# LumaFix64_Vic85to65.net
KiCad netlist of a schematic drawn in EAGLE
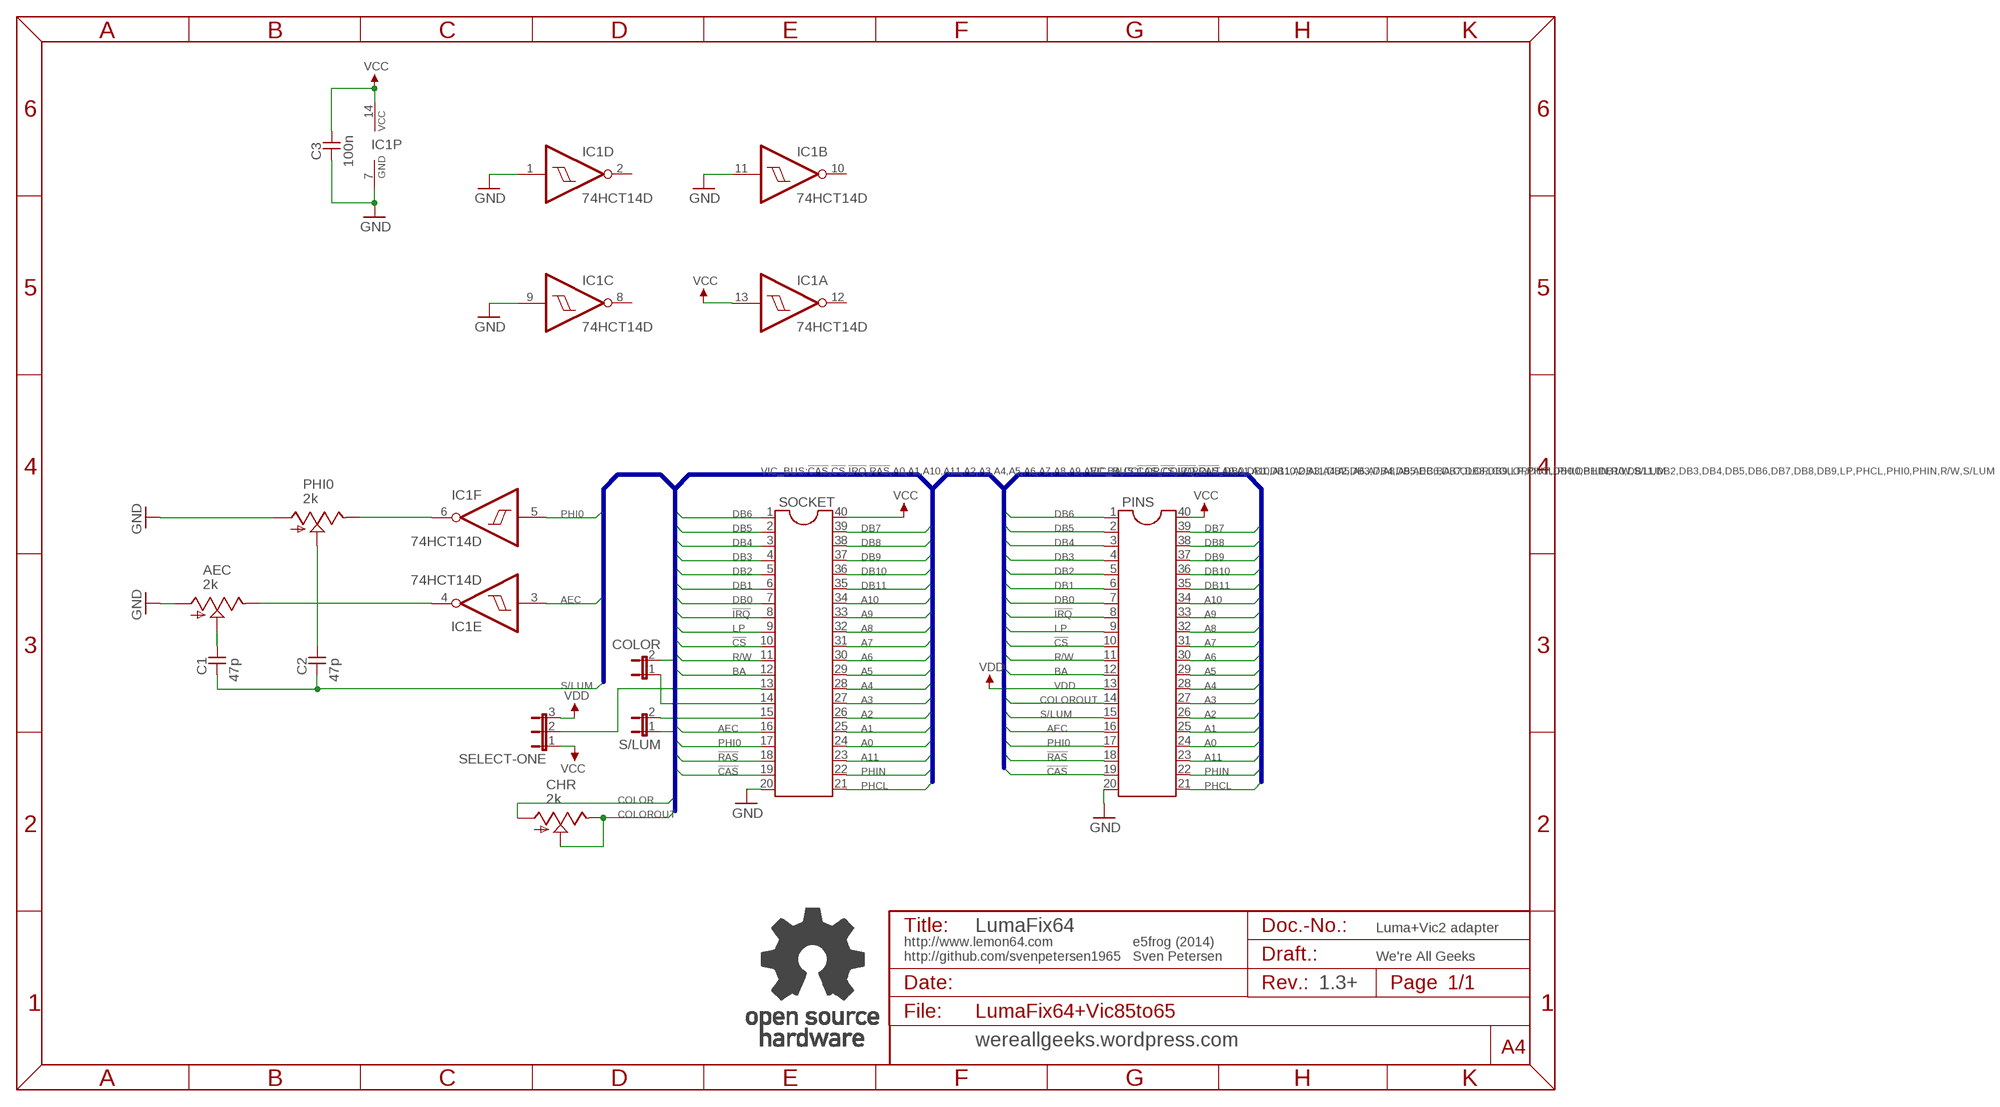
[diagram p0: schematic, sheet 1]

(export (version "E")
  (design (tool "Eeschema 10.0.6"))
  (components
    (comp (ref "AEC")
      (value "2k")
      (footprint "eagle-import:RJ9W")
      (libsource (lib "eagle-import") (part "TRIM_US-RJ9W"))
    )
    (comp (ref "C1")
      (value "47p")
      (footprint "eagle-import:0805")
      (libsource (lib "eagle-import") (part "C-0805"))
    )
    (comp (ref "C2")
      (value "47p")
      (footprint "eagle-import:0805")
      (libsource (lib "eagle-import") (part "C-0805"))
    )
    (comp (ref "C3")
      (value "100n")
      (footprint "eagle-import:0805")
      (libsource (lib "eagle-import") (part "C-0805"))
    )
    (comp (ref "CHR")
      (value "2k")
      (footprint "eagle-import:RJ9W")
      (libsource (lib "eagle-import") (part "TRIM_US-RJ9W"))
    )
    (comp (ref "COLOR")
      (value "JP1E")
      (footprint "eagle-import:JP1")
      (libsource (lib "eagle-import") (part "JP1E"))
    )
    (comp (ref "IC1")
      (value "74HCT14D")
      (footprint "eagle-import:SO14")
      (libsource (lib "eagle-import") (part "7414DHCT"))
    )
    (comp (ref "PHI0")
      (value "2k")
      (footprint "eagle-import:RJ9W")
      (libsource (lib "eagle-import") (part "TRIM_US-RJ9W"))
    )
    (comp (ref "PINS")
      (value "IC-PACKAGE_DIL40_10120540")
      (footprint "eagle-import:BLK_10120540_2X20")
      (libsource (lib "eagle-import") (part "IC-PACKAGE_DIL40_10120540"))
    )
    (comp (ref "S/LUM")
      (value "JP1E")
      (footprint "eagle-import:JP1")
      (libsource (lib "eagle-import") (part "JP1E"))
    )
    (comp (ref "SELECT-ONE")
      (value "JP2E")
      (footprint "eagle-import:JP2")
      (libsource (lib "eagle-import") (part "JP2E"))
    )
    (comp (ref "SOCKET")
      (value "IC-PACKAGE_DIL40GS40P")
      (footprint "eagle-import:GS40P")
      (libsource (lib "eagle-import") (part "IC-PACKAGE_DIL40GS40P"))
    )
    (comp (ref "U$13")
      (value "OPEN_SOURCE_HW")
      (footprint "eagle-import:OPENHW")
      (libsource (lib "eagle-import") (part "OPEN_SOURCE_HW"))
    )
  )
  (nets
    (net (code "2") (name "/A0") (class "Default")
      (node (ref "PINS") (pin "24") (pinfunction "24_24") (pintype "passive"))
      (node (ref "SOCKET") (pin "24") (pinfunction "24_24") (pintype "passive"))
    )
    (net (code "3") (name "/A1") (class "Default")
      (node (ref "PINS") (pin "25") (pinfunction "25_25") (pintype "passive"))
      (node (ref "SOCKET") (pin "25") (pinfunction "25_25") (pintype "passive"))
    )
    (net (code "4") (name "/A2") (class "Default")
      (node (ref "PINS") (pin "26") (pinfunction "26_26") (pintype "passive"))
      (node (ref "SOCKET") (pin "26") (pinfunction "26_26") (pintype "passive"))
    )
    (net (code "5") (name "/A3") (class "Default")
      (node (ref "PINS") (pin "27") (pinfunction "27_27") (pintype "passive"))
      (node (ref "SOCKET") (pin "27") (pinfunction "27_27") (pintype "passive"))
    )
    (net (code "6") (name "/A4") (class "Default")
      (node (ref "PINS") (pin "28") (pinfunction "28_28") (pintype "passive"))
      (node (ref "SOCKET") (pin "28") (pinfunction "28_28") (pintype "passive"))
    )
    (net (code "7") (name "/A5") (class "Default")
      (node (ref "PINS") (pin "29") (pinfunction "29_29") (pintype "passive"))
      (node (ref "SOCKET") (pin "29") (pinfunction "29_29") (pintype "passive"))
    )
    (net (code "8") (name "/A6") (class "Default")
      (node (ref "PINS") (pin "30") (pinfunction "30_30") (pintype "passive"))
      (node (ref "SOCKET") (pin "30") (pinfunction "30_30") (pintype "passive"))
    )
    (net (code "9") (name "/A7") (class "Default")
      (node (ref "PINS") (pin "31") (pinfunction "31_31") (pintype "passive"))
      (node (ref "SOCKET") (pin "31") (pinfunction "31_31") (pintype "passive"))
    )
    (net (code "10") (name "/A8") (class "Default")
      (node (ref "PINS") (pin "32") (pinfunction "32_32") (pintype "passive"))
      (node (ref "SOCKET") (pin "32") (pinfunction "32_32") (pintype "passive"))
    )
    (net (code "11") (name "/A9") (class "Default")
      (node (ref "PINS") (pin "33") (pinfunction "33_33") (pintype "passive"))
      (node (ref "SOCKET") (pin "33") (pinfunction "33_33") (pintype "passive"))
    )
    (net (code "12") (name "/A10") (class "Default")
      (node (ref "PINS") (pin "34") (pinfunction "34_34") (pintype "passive"))
      (node (ref "SOCKET") (pin "34") (pinfunction "34_34") (pintype "passive"))
    )
    (net (code "13") (name "/A11") (class "Default")
      (node (ref "PINS") (pin "23") (pinfunction "23_23") (pintype "passive"))
      (node (ref "SOCKET") (pin "23") (pinfunction "23_23") (pintype "passive"))
    )
    (net (code "14") (name "/AEC") (class "Default")
      (node (ref "IC1") (pin "3") (pinfunction "I_3") (pintype "input"))
      (node (ref "PINS") (pin "16") (pinfunction "16_16") (pintype "passive"))
      (node (ref "SOCKET") (pin "16") (pinfunction "16_16") (pintype "passive"))
    )
    (net (code "15") (name "/BA") (class "Default")
      (node (ref "PINS") (pin "12") (pinfunction "12_12") (pintype "passive"))
      (node (ref "SOCKET") (pin "12") (pinfunction "12_12") (pintype "passive"))
    )
    (net (code "16") (name "/COLOR") (class "Default")
      (node (ref "CHR") (pin "A") (pinfunction "A_A") (pintype "passive"))
      (node (ref "COLOR") (pin "2") (pinfunction "2_2") (pintype "passive"))
    )
    (net (code "17") (name "/COLOROUT") (class "Default")
      (node (ref "CHR") (pin "E") (pinfunction "E_E") (pintype "passive"))
      (node (ref "CHR") (pin "S") (pinfunction "S_S") (pintype "passive"))
      (node (ref "PINS") (pin "14") (pinfunction "14_14") (pintype "passive"))
    )
    (net (code "18") (name "/DB0") (class "Default")
      (node (ref "PINS") (pin "7") (pinfunction "7_7") (pintype "passive"))
      (node (ref "SOCKET") (pin "7") (pinfunction "7_7") (pintype "passive"))
    )
    (net (code "19") (name "/DB1") (class "Default")
      (node (ref "PINS") (pin "6") (pinfunction "6_6") (pintype "passive"))
      (node (ref "SOCKET") (pin "6") (pinfunction "6_6") (pintype "passive"))
    )
    (net (code "20") (name "/DB2") (class "Default")
      (node (ref "PINS") (pin "5") (pinfunction "5_5") (pintype "passive"))
      (node (ref "SOCKET") (pin "5") (pinfunction "5_5") (pintype "passive"))
    )
    (net (code "21") (name "/DB3") (class "Default")
      (node (ref "PINS") (pin "4") (pinfunction "4_4") (pintype "passive"))
      (node (ref "SOCKET") (pin "4") (pinfunction "4_4") (pintype "passive"))
    )
    (net (code "22") (name "/DB4") (class "Default")
      (node (ref "PINS") (pin "3") (pinfunction "3_3") (pintype "passive"))
      (node (ref "SOCKET") (pin "3") (pinfunction "3_3") (pintype "passive"))
    )
    (net (code "23") (name "/DB5") (class "Default")
      (node (ref "PINS") (pin "2") (pinfunction "2_2") (pintype "passive"))
      (node (ref "SOCKET") (pin "2") (pinfunction "2_2") (pintype "passive"))
    )
    (net (code "24") (name "/DB6") (class "Default")
      (node (ref "PINS") (pin "1") (pinfunction "1_1") (pintype "passive"))
      (node (ref "SOCKET") (pin "1") (pinfunction "1_1") (pintype "passive"))
    )
    (net (code "25") (name "/DB7") (class "Default")
      (node (ref "PINS") (pin "39") (pinfunction "39_39") (pintype "passive"))
      (node (ref "SOCKET") (pin "39") (pinfunction "39_39") (pintype "passive"))
    )
    (net (code "26") (name "/DB8") (class "Default")
      (node (ref "PINS") (pin "38") (pinfunction "38_38") (pintype "passive"))
      (node (ref "SOCKET") (pin "38") (pinfunction "38_38") (pintype "passive"))
    )
    (net (code "27") (name "/DB9") (class "Default")
      (node (ref "PINS") (pin "37") (pinfunction "37_37") (pintype "passive"))
      (node (ref "SOCKET") (pin "37") (pinfunction "37_37") (pintype "passive"))
    )
    (net (code "28") (name "/DB10") (class "Default")
      (node (ref "PINS") (pin "36") (pinfunction "36_36") (pintype "passive"))
      (node (ref "SOCKET") (pin "36") (pinfunction "36_36") (pintype "passive"))
    )
    (net (code "29") (name "/DB11") (class "Default")
      (node (ref "PINS") (pin "35") (pinfunction "35_35") (pintype "passive"))
      (node (ref "SOCKET") (pin "35") (pinfunction "35_35") (pintype "passive"))
    )
    (net (code "30") (name "/LP") (class "Default")
      (node (ref "PINS") (pin "9") (pinfunction "9_9") (pintype "passive"))
      (node (ref "SOCKET") (pin "9") (pinfunction "9_9") (pintype "passive"))
    )
    (net (code "31") (name "/PHCL") (class "Default")
      (node (ref "PINS") (pin "21") (pinfunction "21_21") (pintype "passive"))
      (node (ref "SOCKET") (pin "21") (pinfunction "21_21") (pintype "passive"))
    )
    (net (code "32") (name "/PHI0") (class "Default")
      (node (ref "IC1") (pin "5") (pinfunction "I_5") (pintype "input"))
      (node (ref "PINS") (pin "17") (pinfunction "17_17") (pintype "passive"))
      (node (ref "SOCKET") (pin "17") (pinfunction "17_17") (pintype "passive"))
    )
    (net (code "33") (name "/PHIN") (class "Default")
      (node (ref "PINS") (pin "22") (pinfunction "22_22") (pintype "passive"))
      (node (ref "SOCKET") (pin "22") (pinfunction "22_22") (pintype "passive"))
    )
    (net (code "34") (name "/R{slash}W") (class "Default")
      (node (ref "PINS") (pin "11") (pinfunction "11_11") (pintype "passive"))
      (node (ref "SOCKET") (pin "11") (pinfunction "11_11") (pintype "passive"))
    )
    (net (code "35") (name "/VIC_BUS:~{CAS}") (class "Default")
      (node (ref "C1") (pin "1") (pinfunction "1_1") (pintype "passive"))
      (node (ref "C2") (pin "1") (pinfunction "1_1") (pintype "passive"))
      (node (ref "PINS") (pin "15") (pinfunction "15_15") (pintype "passive"))
      (node (ref "S/LUM") (pin "1") (pinfunction "1_1") (pintype "passive"))
    )
    (net (code "37") (name "/~{CAS}") (class "Default")
      (node (ref "PINS") (pin "19") (pinfunction "19_19") (pintype "passive"))
      (node (ref "SOCKET") (pin "19") (pinfunction "19_19") (pintype "passive"))
    )
    (net (code "38") (name "/~{CS}") (class "Default")
      (node (ref "PINS") (pin "10") (pinfunction "10_10") (pintype "passive"))
      (node (ref "SOCKET") (pin "10") (pinfunction "10_10") (pintype "passive"))
    )
    (net (code "39") (name "/~{IRQ}") (class "Default")
      (node (ref "PINS") (pin "8") (pinfunction "8_8") (pintype "passive"))
      (node (ref "SOCKET") (pin "8") (pinfunction "8_8") (pintype "passive"))
    )
    (net (code "40") (name "/~{RAS}") (class "Default")
      (node (ref "PINS") (pin "18") (pinfunction "18_18") (pintype "passive"))
      (node (ref "SOCKET") (pin "18") (pinfunction "18_18") (pintype "passive"))
    )
    (net (code "41") (name "GND") (class "Default")
      (node (ref "AEC") (pin "A") (pinfunction "A_A") (pintype "passive"))
      (node (ref "C3") (pin "1") (pinfunction "1_1") (pintype "passive"))
      (node (ref "IC1") (pin "1") (pinfunction "I_1") (pintype "input"))
      (node (ref "IC1") (pin "11") (pinfunction "I_11") (pintype "input"))
      (node (ref "IC1") (pin "7") (pinfunction "GND_7") (pintype "power_in"))
      (node (ref "IC1") (pin "9") (pinfunction "I_9") (pintype "input"))
      (node (ref "PHI0") (pin "A") (pinfunction "A_A") (pintype "passive"))
      (node (ref "PINS") (pin "20") (pinfunction "20_20") (pintype "passive"))
      (node (ref "SOCKET") (pin "20") (pinfunction "20_20") (pintype "passive"))
    )
    (net (code "42") (name "Net-(AEC-PadS)") (class "Default")
      (node (ref "AEC") (pin "S") (pinfunction "S_S") (pintype "passive"))
      (node (ref "C1") (pin "2") (pinfunction "2_2") (pintype "passive"))
    )
    (net (code "43") (name "Net-(C2-Pad2)") (class "Default")
      (node (ref "C2") (pin "2") (pinfunction "2_2") (pintype "passive"))
      (node (ref "PHI0") (pin "S") (pinfunction "S_S") (pintype "passive"))
    )
    (net (code "44") (name "Net-(COLOR-Pad1)") (class "Default")
      (node (ref "COLOR") (pin "1") (pinfunction "1_1") (pintype "passive"))
      (node (ref "SOCKET") (pin "14") (pinfunction "14_14") (pintype "passive"))
    )
    (net (code "45") (name "Net-(IC1E-O)") (class "Default")
      (node (ref "AEC") (pin "E") (pinfunction "E_E") (pintype "passive"))
      (node (ref "IC1") (pin "4") (pinfunction "O_4") (pintype "output"))
    )
    (net (code "46") (name "Net-(IC1F-O)") (class "Default")
      (node (ref "IC1") (pin "6") (pinfunction "O_6") (pintype "output"))
      (node (ref "PHI0") (pin "E") (pinfunction "E_E") (pintype "passive"))
    )
    (net (code "47") (name "Net-(S/LUM-Pad2)") (class "Default")
      (node (ref "S/LUM") (pin "2") (pinfunction "2_2") (pintype "passive"))
      (node (ref "SOCKET") (pin "15") (pinfunction "15_15") (pintype "passive"))
    )
    (net (code "48") (name "Net-(SELECT-ONE-Pad2)") (class "Default")
      (node (ref "SELECT-ONE") (pin "2") (pinfunction "2_2") (pintype "passive"))
      (node (ref "SOCKET") (pin "13") (pinfunction "13_13") (pintype "passive"))
    )
    (net (code "49") (name "VCC") (class "Default")
      (node (ref "C3") (pin "2") (pinfunction "2_2") (pintype "passive"))
      (node (ref "IC1") (pin "13") (pinfunction "I_13") (pintype "input"))
      (node (ref "IC1") (pin "14") (pinfunction "VCC_14") (pintype "power_in"))
      (node (ref "PINS") (pin "40") (pinfunction "40_40") (pintype "passive"))
      (node (ref "SELECT-ONE") (pin "1") (pinfunction "1_1") (pintype "passive"))
      (node (ref "SOCKET") (pin "40") (pinfunction "40_40") (pintype "passive"))
    )
    (net (code "50") (name "VDD") (class "Default")
      (node (ref "PINS") (pin "13") (pinfunction "13_13") (pintype "passive"))
      (node (ref "SELECT-ONE") (pin "3") (pinfunction "3_3") (pintype "passive"))
    )
    (net (code "51") (name "unconnected-(IC1A-O-Pad12)") (class "Default")
      (node (ref "IC1") (pin "12") (pinfunction "O_12") (pintype "output"))
    )
    (net (code "52") (name "unconnected-(IC1B-O-Pad10)") (class "Default")
      (node (ref "IC1") (pin "10") (pinfunction "O_10") (pintype "output"))
    )
    (net (code "53") (name "unconnected-(IC1C-O-Pad8)") (class "Default")
      (node (ref "IC1") (pin "8") (pinfunction "O_8") (pintype "output"))
    )
    (net (code "54") (name "unconnected-(IC1D-O-Pad2)") (class "Default")
      (node (ref "IC1") (pin "2") (pinfunction "O_2") (pintype "output"))
    )
  )
)
